# CAN_Line.net
KiCad netlist of a schematic drawn in EAGLE
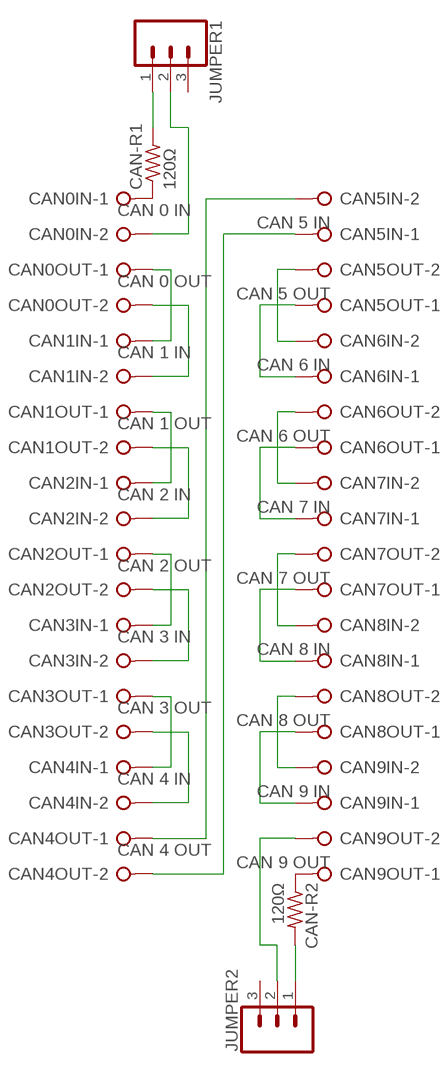
[diagram p0: schematic, sheet 1]

(export (version "E")
  (design (tool "Eeschema 10.0.6"))
  (components
    (comp (ref "CAN-R1")
      (value "120Ω")
      (footprint "eagle-import:0207_10")
      (libsource (lib "eagle-import") (part "R-US_0207/10"))
    )
    (comp (ref "CAN-R2")
      (value "120Ω")
      (footprint "eagle-import:0207_10")
      (libsource (lib "eagle-import") (part "R-US_0207/10"))
    )
    (comp (ref "CAN0IN")
      (value "CAN 0 IN")
      (footprint "eagle-import:W237-132")
      (libsource (lib "eagle-import") (part "W237-02P"))
    )
    (comp (ref "CAN0OUT")
      (value "CAN 0 OUT")
      (footprint "eagle-import:W237-132")
      (libsource (lib "eagle-import") (part "W237-02P"))
    )
    (comp (ref "CAN1IN")
      (value "CAN 1 IN")
      (footprint "eagle-import:W237-132")
      (libsource (lib "eagle-import") (part "W237-02P"))
    )
    (comp (ref "CAN1OUT")
      (value "CAN 1 OUT")
      (footprint "eagle-import:W237-132")
      (libsource (lib "eagle-import") (part "W237-02P"))
    )
    (comp (ref "CAN2IN")
      (value "CAN 2 IN")
      (footprint "eagle-import:W237-132")
      (libsource (lib "eagle-import") (part "W237-02P"))
    )
    (comp (ref "CAN2OUT")
      (value "CAN 2 OUT")
      (footprint "eagle-import:W237-132")
      (libsource (lib "eagle-import") (part "W237-02P"))
    )
    (comp (ref "CAN3IN")
      (value "CAN 3 IN")
      (footprint "eagle-import:W237-132")
      (libsource (lib "eagle-import") (part "W237-02P"))
    )
    (comp (ref "CAN3OUT")
      (value "CAN 3 OUT")
      (footprint "eagle-import:W237-132")
      (libsource (lib "eagle-import") (part "W237-02P"))
    )
    (comp (ref "CAN4IN")
      (value "CAN 4 IN")
      (footprint "eagle-import:W237-132")
      (libsource (lib "eagle-import") (part "W237-02P"))
    )
    (comp (ref "CAN4OUT")
      (value "CAN 4 OUT")
      (footprint "eagle-import:W237-132")
      (libsource (lib "eagle-import") (part "W237-02P"))
    )
    (comp (ref "CAN5IN")
      (value "CAN 5 IN")
      (footprint "eagle-import:W237-132")
      (libsource (lib "eagle-import") (part "W237-02P"))
    )
    (comp (ref "CAN5OUT")
      (value "CAN 5 OUT")
      (footprint "eagle-import:W237-132")
      (libsource (lib "eagle-import") (part "W237-02P"))
    )
    (comp (ref "CAN6IN")
      (value "CAN 6 IN")
      (footprint "eagle-import:W237-132")
      (libsource (lib "eagle-import") (part "W237-02P"))
    )
    (comp (ref "CAN6OUT")
      (value "CAN 6 OUT")
      (footprint "eagle-import:W237-132")
      (libsource (lib "eagle-import") (part "W237-02P"))
    )
    (comp (ref "CAN7IN")
      (value "CAN 7 IN")
      (footprint "eagle-import:W237-132")
      (libsource (lib "eagle-import") (part "W237-02P"))
    )
    (comp (ref "CAN7OUT")
      (value "CAN 7 OUT")
      (footprint "eagle-import:W237-132")
      (libsource (lib "eagle-import") (part "W237-02P"))
    )
    (comp (ref "CAN8IN")
      (value "CAN 8 IN")
      (footprint "eagle-import:W237-132")
      (libsource (lib "eagle-import") (part "W237-02P"))
    )
    (comp (ref "CAN8OUT")
      (value "CAN 8 OUT")
      (footprint "eagle-import:W237-132")
      (libsource (lib "eagle-import") (part "W237-02P"))
    )
    (comp (ref "CAN9IN")
      (value "CAN 9 IN")
      (footprint "eagle-import:W237-132")
      (libsource (lib "eagle-import") (part "W237-02P"))
    )
    (comp (ref "CAN9OUT")
      (value "CAN 9 OUT")
      (footprint "eagle-import:W237-132")
      (libsource (lib "eagle-import") (part "W237-02P"))
    )
    (comp (ref "JUMPER1")
      (value "CONN_03")
      (footprint "eagle-import:1X03")
      (libsource (lib "eagle-import") (part "CONN_03"))
    )
    (comp (ref "JUMPER2")
      (value "CONN_03")
      (footprint "eagle-import:1X03")
      (libsource (lib "eagle-import") (part "CONN_03"))
    )
  )
  (nets
    (net (code "1") (name "Net-(CAN-R1-Pad2)") (class "Default")
      (node (ref "CAN-R1") (pin "2") (pinfunction "2_2") (pintype "passive"))
      (node (ref "JUMPER1") (pin "1") (pinfunction "1_1") (pintype "passive"))
    )
    (net (code "2") (name "Net-(CAN-R2-Pad2)") (class "Default")
      (node (ref "CAN-R2") (pin "2") (pinfunction "2_2") (pintype "passive"))
      (node (ref "JUMPER2") (pin "1") (pinfunction "1_1") (pintype "passive"))
    )
    (net (code "3") (name "Net-(CAN0INA-KL)") (class "Default")
      (node (ref "CAN-R1") (pin "1") (pinfunction "1_1") (pintype "passive"))
      (node (ref "CAN0IN") (pin "1") (pinfunction "KL_1") (pintype "passive"))
    )
    (net (code "4") (name "Net-(CAN0INB-KL)") (class "Default")
      (node (ref "CAN0IN") (pin "2") (pinfunction "KL_2") (pintype "passive"))
      (node (ref "JUMPER1") (pin "2") (pinfunction "2_2") (pintype "passive"))
    )
    (net (code "5") (name "Net-(CAN0OUTA-KL)") (class "Default")
      (node (ref "CAN0OUT") (pin "1") (pinfunction "KL_1") (pintype "passive"))
      (node (ref "CAN1IN") (pin "1") (pinfunction "KL_1") (pintype "passive"))
    )
    (net (code "6") (name "Net-(CAN0OUTB-KL)") (class "Default")
      (node (ref "CAN0OUT") (pin "2") (pinfunction "KL_2") (pintype "passive"))
      (node (ref "CAN1IN") (pin "2") (pinfunction "KL_2") (pintype "passive"))
    )
    (net (code "7") (name "Net-(CAN1OUTA-KL)") (class "Default")
      (node (ref "CAN1OUT") (pin "1") (pinfunction "KL_1") (pintype "passive"))
      (node (ref "CAN2IN") (pin "1") (pinfunction "KL_1") (pintype "passive"))
    )
    (net (code "8") (name "Net-(CAN1OUTB-KL)") (class "Default")
      (node (ref "CAN1OUT") (pin "2") (pinfunction "KL_2") (pintype "passive"))
      (node (ref "CAN2IN") (pin "2") (pinfunction "KL_2") (pintype "passive"))
    )
    (net (code "9") (name "Net-(CAN2OUTA-KL)") (class "Default")
      (node (ref "CAN2OUT") (pin "1") (pinfunction "KL_1") (pintype "passive"))
      (node (ref "CAN3IN") (pin "1") (pinfunction "KL_1") (pintype "passive"))
    )
    (net (code "10") (name "Net-(CAN2OUTB-KL)") (class "Default")
      (node (ref "CAN2OUT") (pin "2") (pinfunction "KL_2") (pintype "passive"))
      (node (ref "CAN3IN") (pin "2") (pinfunction "KL_2") (pintype "passive"))
    )
    (net (code "11") (name "Net-(CAN3OUTA-KL)") (class "Default")
      (node (ref "CAN3OUT") (pin "1") (pinfunction "KL_1") (pintype "passive"))
      (node (ref "CAN4IN") (pin "1") (pinfunction "KL_1") (pintype "passive"))
    )
    (net (code "12") (name "Net-(CAN3OUTB-KL)") (class "Default")
      (node (ref "CAN3OUT") (pin "2") (pinfunction "KL_2") (pintype "passive"))
      (node (ref "CAN4IN") (pin "2") (pinfunction "KL_2") (pintype "passive"))
    )
    (net (code "13") (name "Net-(CAN4OUTA-KL)") (class "Default")
      (node (ref "CAN4OUT") (pin "1") (pinfunction "KL_1") (pintype "passive"))
      (node (ref "CAN5IN") (pin "2") (pinfunction "KL_2") (pintype "passive"))
    )
    (net (code "14") (name "Net-(CAN4OUTB-KL)") (class "Default")
      (node (ref "CAN4OUT") (pin "2") (pinfunction "KL_2") (pintype "passive"))
      (node (ref "CAN5IN") (pin "1") (pinfunction "KL_1") (pintype "passive"))
    )
    (net (code "15") (name "Net-(CAN5OUTA-KL)") (class "Default")
      (node (ref "CAN5OUT") (pin "1") (pinfunction "KL_1") (pintype "passive"))
      (node (ref "CAN6IN") (pin "1") (pinfunction "KL_1") (pintype "passive"))
    )
    (net (code "16") (name "Net-(CAN5OUTB-KL)") (class "Default")
      (node (ref "CAN5OUT") (pin "2") (pinfunction "KL_2") (pintype "passive"))
      (node (ref "CAN6IN") (pin "2") (pinfunction "KL_2") (pintype "passive"))
    )
    (net (code "17") (name "Net-(CAN6OUTA-KL)") (class "Default")
      (node (ref "CAN6OUT") (pin "1") (pinfunction "KL_1") (pintype "passive"))
      (node (ref "CAN7IN") (pin "1") (pinfunction "KL_1") (pintype "passive"))
    )
    (net (code "18") (name "Net-(CAN6OUTB-KL)") (class "Default")
      (node (ref "CAN6OUT") (pin "2") (pinfunction "KL_2") (pintype "passive"))
      (node (ref "CAN7IN") (pin "2") (pinfunction "KL_2") (pintype "passive"))
    )
    (net (code "19") (name "Net-(CAN7OUTA-KL)") (class "Default")
      (node (ref "CAN7OUT") (pin "1") (pinfunction "KL_1") (pintype "passive"))
      (node (ref "CAN8IN") (pin "1") (pinfunction "KL_1") (pintype "passive"))
    )
    (net (code "20") (name "Net-(CAN7OUTB-KL)") (class "Default")
      (node (ref "CAN7OUT") (pin "2") (pinfunction "KL_2") (pintype "passive"))
      (node (ref "CAN8IN") (pin "2") (pinfunction "KL_2") (pintype "passive"))
    )
    (net (code "21") (name "Net-(CAN8OUTA-KL)") (class "Default")
      (node (ref "CAN8OUT") (pin "1") (pinfunction "KL_1") (pintype "passive"))
      (node (ref "CAN9IN") (pin "1") (pinfunction "KL_1") (pintype "passive"))
    )
    (net (code "22") (name "Net-(CAN8OUTB-KL)") (class "Default")
      (node (ref "CAN8OUT") (pin "2") (pinfunction "KL_2") (pintype "passive"))
      (node (ref "CAN9IN") (pin "2") (pinfunction "KL_2") (pintype "passive"))
    )
    (net (code "23") (name "Net-(CAN9OUTA-KL)") (class "Default")
      (node (ref "CAN-R2") (pin "1") (pinfunction "1_1") (pintype "passive"))
      (node (ref "CAN9OUT") (pin "1") (pinfunction "KL_1") (pintype "passive"))
    )
    (net (code "24") (name "Net-(CAN9OUTB-KL)") (class "Default")
      (node (ref "CAN9OUT") (pin "2") (pinfunction "KL_2") (pintype "passive"))
      (node (ref "JUMPER2") (pin "2") (pinfunction "2_2") (pintype "passive"))
    )
    (net (code "25") (name "unconnected-(JUMPER1-Pad3)") (class "Default")
      (node (ref "JUMPER1") (pin "3") (pinfunction "3_3") (pintype "passive"))
    )
    (net (code "26") (name "unconnected-(JUMPER2-Pad3)") (class "Default")
      (node (ref "JUMPER2") (pin "3") (pinfunction "3_3") (pintype "passive"))
    )
  )
)
